# Totem_Teensy.net
KiCad netlist of a schematic drawn in EAGLE
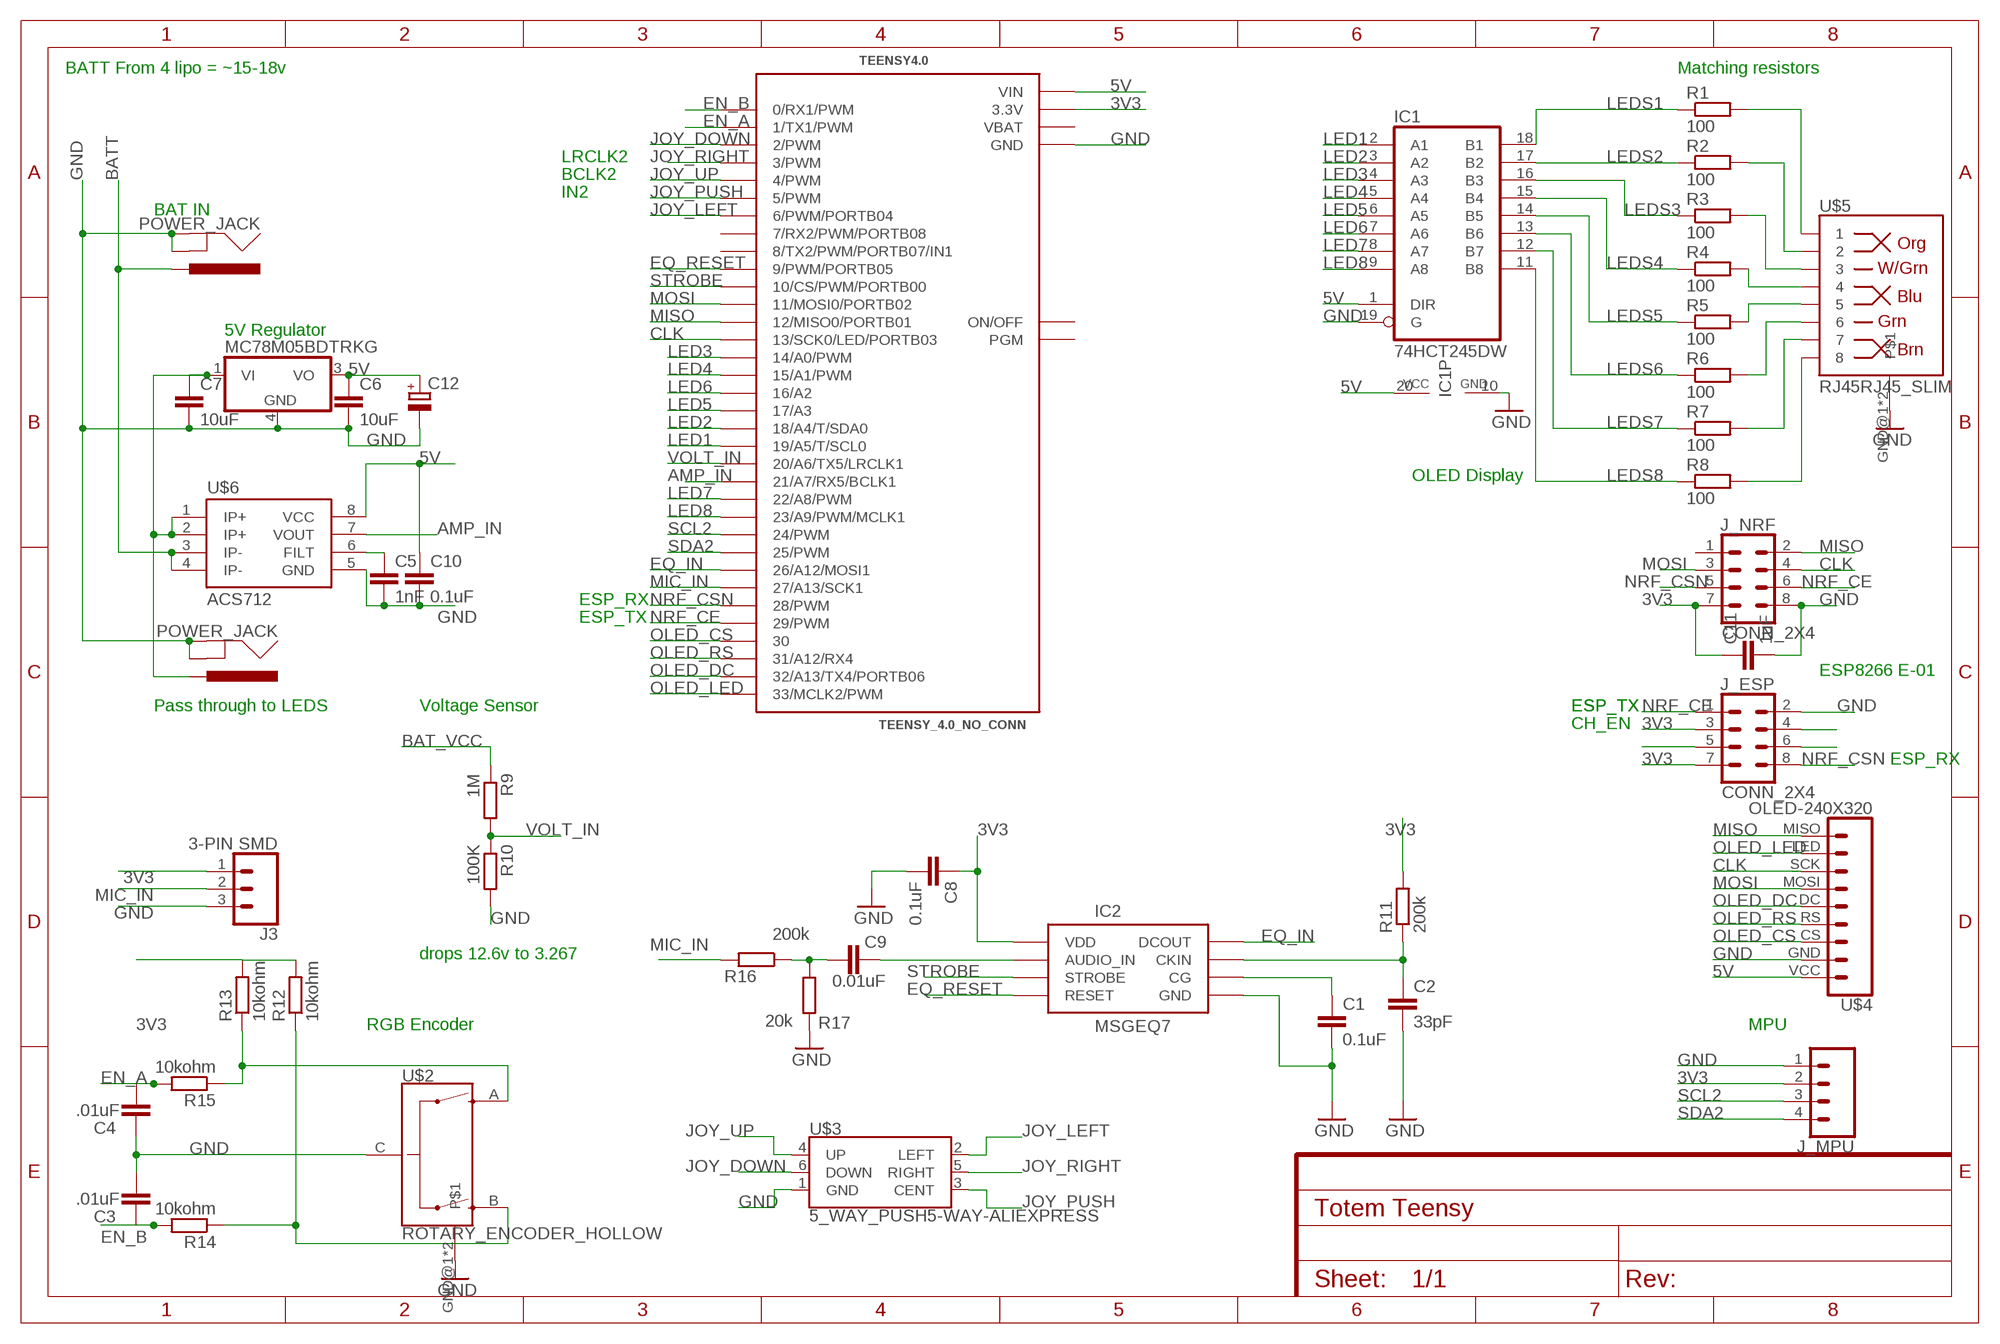
[diagram p0: schematic, sheet 1]

(export (version "E")
  (design (tool "Eeschema 10.0.6"))
  (components
    (comp (ref "C1")
      (value "0.1uF")
      (footprint "eagle-import:C1206")
      (libsource (lib "eagle-import") (part "CC1206"))
    )
    (comp (ref "C2")
      (value "33pF")
      (footprint "eagle-import:C1206")
      (libsource (lib "eagle-import") (part "CC1206"))
    )
    (comp (ref "C3")
      (value ".01uF")
      (footprint "eagle-import:C1206")
      (libsource (lib "eagle-import") (part "CC1206"))
    )
    (comp (ref "C4")
      (value ".01uF")
      (footprint "eagle-import:C1206")
      (libsource (lib "eagle-import") (part "CC1206"))
    )
    (comp (ref "C5")
      (value "1nF")
      (footprint "eagle-import:C1206")
      (libsource (lib "eagle-import") (part "CC1206"))
    )
    (comp (ref "C6")
      (value "10uF")
      (footprint "eagle-import:C1206")
      (libsource (lib "eagle-import") (part "C-EUC1206"))
    )
    (comp (ref "C7")
      (value "10uF")
      (footprint "eagle-import:C1206")
      (libsource (lib "eagle-import") (part "C-EUC1206"))
    )
    (comp (ref "C8")
      (value "0.1uF")
      (footprint "eagle-import:C1206")
      (libsource (lib "eagle-import") (part "CC1206"))
    )
    (comp (ref "C9")
      (value "0.01uF")
      (footprint "eagle-import:C1206")
      (libsource (lib "eagle-import") (part "CC1206"))
    )
    (comp (ref "C10")
      (value "0.1uF")
      (footprint "eagle-import:C1206")
      (libsource (lib "eagle-import") (part "CC1206"))
    )
    (comp (ref "C11")
      (value "1uF")
      (footprint "eagle-import:C1206")
      (libsource (lib "eagle-import") (part "C-EUC1206"))
    )
    (comp (ref "C12")
      (value "CPOL-EUTT2D5L")
      (footprint "eagle-import:TT2D5L")
      (libsource (lib "eagle-import") (part "CPOL-EUTT2D5L"))
    )
    (comp (ref "IC1")
      (value "74HCT245DW")
      (footprint "eagle-import:SO20W")
      (libsource (lib "eagle-import") (part "74245DWHCT"))
    )
    (comp (ref "IC2")
      (value "MSGEQ7DIP")
      (footprint "eagle-import:DIL08")
      (libsource (lib "eagle-import") (part "MSGEQ7DIP"))
    )
    (comp (ref "IC3")
      (value "MC78M05BDTRKG")
      (footprint "eagle-import:DPACK_3")
      (libsource (lib "eagle-import") (part "MC78M05BDTRKG"))
    )
    (comp (ref "J1")
      (value "POWER_JACK")
      (footprint "eagle-import:POWER_JACK_PTH")
      (libsource (lib "eagle-import") (part "POWER_JACK"))
    )
    (comp (ref "J3")
      (value "3-PIN SMD")
      (footprint "eagle-import:JST-3-SMD")
      (libsource (lib "eagle-import") (part "CONN_03JST-SMD"))
    )
    (comp (ref "J7")
      (value "POWER_JACK")
      (footprint "eagle-import:POWER_JACK_PTH")
      (libsource (lib "eagle-import") (part "POWER_JACK"))
    )
    (comp (ref "J_ESP")
      (value "CONN_2X4")
      (footprint "eagle-import:2X4")
      (libsource (lib "eagle-import") (part "CONN_2X4"))
    )
    (comp (ref "J_MPU")
      (value "CONN_04")
      (footprint "eagle-import:1X04")
      (libsource (lib "eagle-import") (part "CONN_04"))
    )
    (comp (ref "J_NRF")
      (value "CONN_2X4")
      (footprint "eagle-import:2X4")
      (libsource (lib "eagle-import") (part "CONN_2X4"))
    )
    (comp (ref "R1")
      (value "100")
      (footprint "eagle-import:R1206")
      (libsource (lib "eagle-import") (part "RR1206"))
    )
    (comp (ref "R2")
      (value "100")
      (footprint "eagle-import:R1206")
      (libsource (lib "eagle-import") (part "RR1206"))
    )
    (comp (ref "R3")
      (value "100")
      (footprint "eagle-import:R1206")
      (libsource (lib "eagle-import") (part "RR1206"))
    )
    (comp (ref "R4")
      (value "100")
      (footprint "eagle-import:R1206")
      (libsource (lib "eagle-import") (part "RR1206"))
    )
    (comp (ref "R5")
      (value "100")
      (footprint "eagle-import:R1206")
      (libsource (lib "eagle-import") (part "RR1206"))
    )
    (comp (ref "R6")
      (value "100")
      (footprint "eagle-import:R1206")
      (libsource (lib "eagle-import") (part "RR1206"))
    )
    (comp (ref "R7")
      (value "100")
      (footprint "eagle-import:R1206")
      (libsource (lib "eagle-import") (part "RR1206"))
    )
    (comp (ref "R8")
      (value "100")
      (footprint "eagle-import:R1206")
      (libsource (lib "eagle-import") (part "RR1206"))
    )
    (comp (ref "R9")
      (value "1M")
      (footprint "eagle-import:M1206")
      (libsource (lib "eagle-import") (part "R-EU_M1206"))
    )
    (comp (ref "R10")
      (value "100K")
      (footprint "eagle-import:M1206")
      (libsource (lib "eagle-import") (part "R-EU_M1206"))
    )
    (comp (ref "R11")
      (value "200k")
      (footprint "eagle-import:R1206")
      (libsource (lib "eagle-import") (part "RR1206"))
    )
    (comp (ref "R12")
      (value "10kohm")
      (footprint "eagle-import:R1206")
      (libsource (lib "eagle-import") (part "RR1206"))
    )
    (comp (ref "R13")
      (value "10kohm")
      (footprint "eagle-import:R1206")
      (libsource (lib "eagle-import") (part "RR1206"))
    )
    (comp (ref "R14")
      (value "10kohm")
      (footprint "eagle-import:R1206")
      (libsource (lib "eagle-import") (part "RR1206"))
    )
    (comp (ref "R15")
      (value "10kohm")
      (footprint "eagle-import:R1206")
      (libsource (lib "eagle-import") (part "RR1206"))
    )
    (comp (ref "R16")
      (value "200k")
      (footprint "eagle-import:R1206")
      (libsource (lib "eagle-import") (part "RR1206"))
    )
    (comp (ref "R17")
      (value "20k")
      (footprint "eagle-import:R1206")
      (libsource (lib "eagle-import") (part "RR1206"))
    )
    (comp (ref "TEENSY4.0")
      (value "TEENSY_4.0_NO_CONN")
      (footprint "eagle-import:TEENSY_4.0")
      (libsource (lib "eagle-import") (part "TEENSY_4.0_NO_CONN"))
    )
    (comp (ref "U$2")
      (value "ROTARY_ENCODER_HOLLOW")
      (footprint "eagle-import:HOLLOW_ENCODER30R")
      (libsource (lib "eagle-import") (part "ROTARY_ENCODER_HOLLOW"))
    )
    (comp (ref "U$3")
      (value "5_WAY_PUSH5-WAY-ALIEXPRESS")
      (footprint "eagle-import:5-WAY_PTH2")
      (libsource (lib "eagle-import") (part "5_WAY_PUSH5-WAY-ALIEXPRESS"))
    )
    (comp (ref "U$4")
      (value "OLED-240X320")
      (footprint "eagle-import:OLED_240X320")
      (libsource (lib "eagle-import") (part "OLED-240X320"))
    )
    (comp (ref "U$5")
      (value "RJ45RJ45_SLIM")
      (footprint "eagle-import:RJ45_SLIM")
      (libsource (lib "eagle-import") (part "RJ45RJ45_SLIM"))
    )
    (comp (ref "U$6")
      (value "ACS712")
      (footprint "eagle-import:SO08")
      (libsource (lib "eagle-import") (part "ACS712"))
    )
  )
  (nets
    (net (code "1") (name "/3V3") (class "Default")
      (node (ref "C11") (pin "1") (pinfunction "1_1") (pintype "passive"))
      (node (ref "C8") (pin "1") (pinfunction "1_1") (pintype "passive"))
      (node (ref "IC2") (pin "1") (pinfunction "VDD_1") (pintype "input"))
      (node (ref "J3") (pin "1") (pinfunction "1_1") (pintype "passive"))
      (node (ref "J_ESP") (pin "3") (pinfunction "3_3") (pintype "passive"))
      (node (ref "J_ESP") (pin "7") (pinfunction "7_7") (pintype "passive"))
      (node (ref "J_MPU") (pin "2") (pinfunction "2_2") (pintype "passive"))
      (node (ref "J_NRF") (pin "7") (pinfunction "7_7") (pintype "passive"))
      (node (ref "R11") (pin "2") (pinfunction "2_2") (pintype "passive"))
      (node (ref "R12") (pin "2") (pinfunction "2_2") (pintype "passive"))
      (node (ref "R13") (pin "2") (pinfunction "2_2") (pintype "passive"))
      (node (ref "TEENSY4.0") (pin "3.3@0") (pinfunction "3.3V_3.3@0") (pintype "power_in"))
      (node (ref "TEENSY4.0") (pin "3.3@1") (pinfunction "3.3V_3.3@1") (pintype "power_in"))
    )
    (net (code "2") (name "/5V") (class "Default")
      (node (ref "C10") (pin "1") (pinfunction "1_1") (pintype "passive"))
      (node (ref "C12") (pin "+") (pinfunction "+_+") (pintype "passive"))
      (node (ref "C6") (pin "1") (pinfunction "1_1") (pintype "passive"))
      (node (ref "IC1") (pin "1") (pinfunction "DIR_1") (pintype "input"))
      (node (ref "IC1") (pin "20") (pinfunction "VCC_20") (pintype "power_in"))
      (node (ref "IC3") (pin "3") (pinfunction "VO_3") (pintype "passive"))
      (node (ref "TEENSY4.0") (pin "VIN") (pinfunction "VIN_VIN") (pintype "power_in"))
      (node (ref "U$4") (pin "VCC") (pinfunction "VCC_VCC") (pintype "passive"))
      (node (ref "U$6") (pin "8") (pinfunction "VCC_8") (pintype "bidirectional"))
    )
    (net (code "3") (name "/AMP_IN") (class "Default")
      (node (ref "TEENSY4.0") (pin "21/A7") (pinfunction "21/A7/RX5/BCLK1_21/A7") (pintype "bidirectional"))
      (node (ref "U$6") (pin "7") (pinfunction "VOUT_7") (pintype "bidirectional"))
    )
    (net (code "4") (name "/BATT") (class "Default")
      (node (ref "J1") (pin "PWR") (pinfunction "PWR_PWR") (pintype "bidirectional"))
      (node (ref "U$6") (pin "3") (pinfunction "IP-_3") (pintype "bidirectional"))
      (node (ref "U$6") (pin "4") (pinfunction "IP-_4") (pintype "bidirectional"))
    )
    (net (code "5") (name "/BAT_VCC") (class "Default")
      (node (ref "C7") (pin "1") (pinfunction "1_1") (pintype "passive"))
      (node (ref "IC3") (pin "1") (pinfunction "VI_1") (pintype "input"))
      (node (ref "J7") (pin "PWR") (pinfunction "PWR_PWR") (pintype "bidirectional"))
      (node (ref "R9") (pin "1") (pinfunction "1_1") (pintype "passive"))
      (node (ref "U$6") (pin "1") (pinfunction "IP+_1") (pintype "bidirectional"))
      (node (ref "U$6") (pin "2") (pinfunction "IP+_2") (pintype "bidirectional"))
    )
    (net (code "6") (name "/CLK") (class "Default")
      (node (ref "J_NRF") (pin "4") (pinfunction "4_4") (pintype "passive"))
      (node (ref "TEENSY4.0") (pin "13") (pinfunction "13/SCK0/LED/PORTB03_13") (pintype "bidirectional"))
      (node (ref "U$4") (pin "SCK") (pinfunction "CLK_SCK") (pintype "passive"))
    )
    (net (code "7") (name "/EN_A") (class "Default")
      (node (ref "C4") (pin "1") (pinfunction "1_1") (pintype "passive"))
      (node (ref "R15") (pin "2") (pinfunction "2_2") (pintype "passive"))
      (node (ref "TEENSY4.0") (pin "1") (pinfunction "1/TX1/PWM_1") (pintype "bidirectional"))
    )
    (net (code "8") (name "/EN_B") (class "Default")
      (node (ref "C3") (pin "2") (pinfunction "2_2") (pintype "passive"))
      (node (ref "R14") (pin "2") (pinfunction "2_2") (pintype "passive"))
      (node (ref "TEENSY4.0") (pin "0") (pinfunction "0/RX1/PWM_0") (pintype "bidirectional"))
    )
    (net (code "9") (name "/EQ_IN") (class "Default")
      (node (ref "IC2") (pin "3") (pinfunction "DCOUT_3") (pintype "bidirectional"))
      (node (ref "TEENSY4.0") (pin "26") (pinfunction "26/A12/MOSI1_26") (pintype "bidirectional"))
    )
    (net (code "10") (name "/EQ_RESET") (class "Default")
      (node (ref "IC2") (pin "7") (pinfunction "RESET_7") (pintype "input"))
      (node (ref "TEENSY4.0") (pin "9") (pinfunction "9/PWM/PORTB05_9") (pintype "bidirectional"))
    )
    (net (code "11") (name "/JOY_DOWN") (class "Default")
      (node (ref "TEENSY4.0") (pin "2") (pinfunction "2/PWM_2") (pintype "bidirectional"))
      (node (ref "U$3") (pin "6") (pinfunction "DOWN_6") (pintype "bidirectional"))
    )
    (net (code "12") (name "/JOY_LEFT") (class "Default")
      (node (ref "TEENSY4.0") (pin "6") (pinfunction "6/PWM/PORTB04_6") (pintype "bidirectional"))
      (node (ref "U$3") (pin "2") (pinfunction "LEFT_2") (pintype "bidirectional"))
    )
    (net (code "13") (name "/JOY_PUSH") (class "Default")
      (node (ref "TEENSY4.0") (pin "5") (pinfunction "5/PWM_5") (pintype "bidirectional"))
      (node (ref "U$3") (pin "3") (pinfunction "CENT_3") (pintype "bidirectional"))
    )
    (net (code "14") (name "/JOY_RIGHT") (class "Default")
      (node (ref "TEENSY4.0") (pin "3") (pinfunction "3/PWM_3") (pintype "bidirectional"))
      (node (ref "U$3") (pin "5") (pinfunction "RIGHT_5") (pintype "bidirectional"))
    )
    (net (code "15") (name "/JOY_UP") (class "Default")
      (node (ref "TEENSY4.0") (pin "4") (pinfunction "4/PWM_4") (pintype "bidirectional"))
      (node (ref "U$3") (pin "4") (pinfunction "UP_4") (pintype "bidirectional"))
    )
    (net (code "16") (name "/LED1") (class "Default")
      (node (ref "IC1") (pin "2") (pinfunction "A1_2") (pintype "bidirectional"))
      (node (ref "TEENSY4.0") (pin "19/A5") (pinfunction "19/A5/T/SCL0_19/A5") (pintype "bidirectional"))
    )
    (net (code "17") (name "/LED2") (class "Default")
      (node (ref "IC1") (pin "3") (pinfunction "A2_3") (pintype "bidirectional"))
      (node (ref "TEENSY4.0") (pin "18/A4") (pinfunction "18/A4/T/SDA0_18/A4") (pintype "bidirectional"))
    )
    (net (code "18") (name "/LED3") (class "Default")
      (node (ref "IC1") (pin "4") (pinfunction "A3_4") (pintype "bidirectional"))
      (node (ref "TEENSY4.0") (pin "14/A0") (pinfunction "14/A0/PWM_14/A0") (pintype "bidirectional"))
    )
    (net (code "19") (name "/LED4") (class "Default")
      (node (ref "IC1") (pin "5") (pinfunction "A4_5") (pintype "bidirectional"))
      (node (ref "TEENSY4.0") (pin "15/A1") (pinfunction "15/A1/PWM_15/A1") (pintype "bidirectional"))
    )
    (net (code "20") (name "/LED5") (class "Default")
      (node (ref "IC1") (pin "6") (pinfunction "A5_6") (pintype "bidirectional"))
      (node (ref "TEENSY4.0") (pin "17/A3") (pinfunction "17/A3_17/A3") (pintype "bidirectional"))
    )
    (net (code "21") (name "/LED6") (class "Default")
      (node (ref "IC1") (pin "7") (pinfunction "A6_7") (pintype "bidirectional"))
      (node (ref "TEENSY4.0") (pin "16/A2") (pinfunction "16/A2_16/A2") (pintype "bidirectional"))
    )
    (net (code "22") (name "/LED7") (class "Default")
      (node (ref "IC1") (pin "8") (pinfunction "A7_8") (pintype "bidirectional"))
      (node (ref "TEENSY4.0") (pin "22/A8") (pinfunction "22/A8/PWM_22/A8") (pintype "bidirectional"))
    )
    (net (code "23") (name "/LED8") (class "Default")
      (node (ref "IC1") (pin "9") (pinfunction "A8_9") (pintype "bidirectional"))
      (node (ref "TEENSY4.0") (pin "23/A9") (pinfunction "23/A9/PWM/MCLK1_23/A9") (pintype "bidirectional"))
    )
    (net (code "24") (name "/LEDS1") (class "Default")
      (node (ref "IC1") (pin "18") (pinfunction "B1_18") (pintype "bidirectional"))
      (node (ref "R1") (pin "1") (pinfunction "1_1") (pintype "passive"))
    )
    (net (code "25") (name "/LEDS2") (class "Default")
      (node (ref "IC1") (pin "17") (pinfunction "B2_17") (pintype "bidirectional"))
      (node (ref "R2") (pin "1") (pinfunction "1_1") (pintype "passive"))
    )
    (net (code "26") (name "/LEDS3") (class "Default")
      (node (ref "IC1") (pin "16") (pinfunction "B3_16") (pintype "bidirectional"))
      (node (ref "R3") (pin "1") (pinfunction "1_1") (pintype "passive"))
    )
    (net (code "27") (name "/LEDS4") (class "Default")
      (node (ref "IC1") (pin "15") (pinfunction "B4_15") (pintype "bidirectional"))
      (node (ref "R4") (pin "1") (pinfunction "1_1") (pintype "passive"))
    )
    (net (code "28") (name "/LEDS5") (class "Default")
      (node (ref "IC1") (pin "14") (pinfunction "B5_14") (pintype "bidirectional"))
      (node (ref "R5") (pin "1") (pinfunction "1_1") (pintype "passive"))
    )
    (net (code "29") (name "/LEDS6") (class "Default")
      (node (ref "IC1") (pin "13") (pinfunction "B6_13") (pintype "bidirectional"))
      (node (ref "R6") (pin "1") (pinfunction "1_1") (pintype "passive"))
    )
    (net (code "30") (name "/LEDS7") (class "Default")
      (node (ref "IC1") (pin "12") (pinfunction "B7_12") (pintype "bidirectional"))
      (node (ref "R7") (pin "1") (pinfunction "1_1") (pintype "passive"))
    )
    (net (code "31") (name "/LEDS8") (class "Default")
      (node (ref "IC1") (pin "11") (pinfunction "B8_11") (pintype "bidirectional"))
      (node (ref "R8") (pin "1") (pinfunction "1_1") (pintype "passive"))
    )
    (net (code "32") (name "/MIC_IN") (class "Default")
      (node (ref "J3") (pin "2") (pinfunction "2_2") (pintype "passive"))
      (node (ref "R16") (pin "2") (pinfunction "2_2") (pintype "passive"))
      (node (ref "TEENSY4.0") (pin "27") (pinfunction "27/A13/SCK1_27") (pintype "bidirectional"))
    )
    (net (code "33") (name "/MISO") (class "Default")
      (node (ref "J_NRF") (pin "2") (pinfunction "2_2") (pintype "passive"))
      (node (ref "TEENSY4.0") (pin "12") (pinfunction "12/MISO0/PORTB01_12") (pintype "bidirectional"))
      (node (ref "U$4") (pin "MISO") (pinfunction "MISO_MISO") (pintype "passive"))
    )
    (net (code "34") (name "/MOSI") (class "Default")
      (node (ref "J_NRF") (pin "3") (pinfunction "3_3") (pintype "passive"))
      (node (ref "TEENSY4.0") (pin "11") (pinfunction "11/MOSI0/PORTB02_11") (pintype "bidirectional"))
      (node (ref "U$4") (pin "MOSI") (pinfunction "MOSI_MOSI") (pintype "passive"))
    )
    (net (code "35") (name "/NRF_CE") (class "Default")
      (node (ref "J_ESP") (pin "1") (pinfunction "1_1") (pintype "passive"))
      (node (ref "J_NRF") (pin "6") (pinfunction "6_6") (pintype "passive"))
      (node (ref "TEENSY4.0") (pin "29") (pinfunction "29/PWM_29") (pintype "bidirectional"))
    )
    (net (code "36") (name "/NRF_CSN") (class "Default")
      (node (ref "J_ESP") (pin "8") (pinfunction "8_8") (pintype "passive"))
      (node (ref "J_NRF") (pin "5") (pinfunction "5_5") (pintype "passive"))
      (node (ref "TEENSY4.0") (pin "28") (pinfunction "28/PWM_28") (pintype "bidirectional"))
    )
    (net (code "37") (name "/OLED_CS") (class "Default")
      (node (ref "TEENSY4.0") (pin "30") (pinfunction "30_30") (pintype "bidirectional"))
      (node (ref "U$4") (pin "CS") (pinfunction "CS_CS") (pintype "passive"))
    )
    (net (code "38") (name "/OLED_DC") (class "Default")
      (node (ref "TEENSY4.0") (pin "32") (pinfunction "32/A13/TX4/PORTB06_32") (pintype "bidirectional"))
      (node (ref "U$4") (pin "DC") (pinfunction "DC_DC") (pintype "passive"))
    )
    (net (code "39") (name "/OLED_LED") (class "Default")
      (node (ref "TEENSY4.0") (pin "33") (pinfunction "33/MCLK2/PWM_33") (pintype "bidirectional"))
      (node (ref "U$4") (pin "LED") (pinfunction "LED_LED") (pintype "passive"))
    )
    (net (code "40") (name "/OLED_RS") (class "Default")
      (node (ref "TEENSY4.0") (pin "31") (pinfunction "31/A12/RX4_31") (pintype "bidirectional"))
      (node (ref "U$4") (pin "RS") (pinfunction "RS_RS") (pintype "passive"))
    )
    (net (code "41") (name "/SCL2") (class "Default")
      (node (ref "J_MPU") (pin "3") (pinfunction "3_3") (pintype "passive"))
      (node (ref "TEENSY4.0") (pin "24") (pinfunction "24/PWM_24") (pintype "bidirectional"))
    )
    (net (code "42") (name "/SDA2") (class "Default")
      (node (ref "J_MPU") (pin "4") (pinfunction "4_4") (pintype "passive"))
      (node (ref "TEENSY4.0") (pin "25") (pinfunction "25/PWM_25") (pintype "bidirectional"))
    )
    (net (code "43") (name "/STROBE") (class "Default")
      (node (ref "IC2") (pin "4") (pinfunction "STROBE_4") (pintype "input"))
      (node (ref "TEENSY4.0") (pin "10") (pinfunction "10/CS/PWM/PORTB00_10") (pintype "bidirectional"))
    )
    (net (code "44") (name "/VBAT") (class "Default")
      (node (ref "TEENSY4.0") (pin "VBAT") (pinfunction "VBAT_VBAT") (pintype "power_in"))
    )
    (net (code "45") (name "/VOLT_IN") (class "Default")
      (node (ref "R10") (pin "1") (pinfunction "1_1") (pintype "passive"))
      (node (ref "R9") (pin "2") (pinfunction "2_2") (pintype "passive"))
      (node (ref "TEENSY4.0") (pin "20/A6") (pinfunction "20/A6/TX5/LRCLK1_20/A6") (pintype "bidirectional"))
    )
    (net (code "46") (name "GND") (class "Default")
      (node (ref "C1") (pin "2") (pinfunction "2_2") (pintype "passive"))
      (node (ref "C10") (pin "2") (pinfunction "2_2") (pintype "passive"))
      (node (ref "C11") (pin "2") (pinfunction "2_2") (pintype "passive"))
      (node (ref "C12") (pin "-") (pinfunction "-_-") (pintype "passive"))
      (node (ref "C2") (pin "2") (pinfunction "2_2") (pintype "passive"))
      (node (ref "C3") (pin "1") (pinfunction "1_1") (pintype "passive"))
      (node (ref "C4") (pin "2") (pinfunction "2_2") (pintype "passive"))
      (node (ref "C5") (pin "2") (pinfunction "2_2") (pintype "passive"))
      (node (ref "C6") (pin "2") (pinfunction "2_2") (pintype "passive"))
      (node (ref "C7") (pin "2") (pinfunction "2_2") (pintype "passive"))
      (node (ref "C8") (pin "2") (pinfunction "2_2") (pintype "passive"))
      (node (ref "IC1") (pin "10") (pinfunction "GND_10") (pintype "power_in"))
      (node (ref "IC1") (pin "19") (pinfunction "G_19") (pintype "input"))
      (node (ref "IC2") (pin "2") (pinfunction "GND_2") (pintype "bidirectional"))
      (node (ref "IC3") (pin "4") (pinfunction "GND_4") (pintype "passive"))
      (node (ref "J1") (pin "GND") (pinfunction "GND_GND") (pintype "bidirectional"))
      (node (ref "J1") (pin "GNDBREAK") (pinfunction "GNDBREAK_GNDBREAK") (pintype "bidirectional"))
      (node (ref "J3") (pin "3") (pinfunction "3_3") (pintype "passive"))
      (node (ref "J7") (pin "GND") (pinfunction "GND_GND") (pintype "bidirectional"))
      (node (ref "J7") (pin "GNDBREAK") (pinfunction "GNDBREAK_GNDBREAK") (pintype "bidirectional"))
      (node (ref "J_ESP") (pin "2") (pinfunction "2_2") (pintype "passive"))
      (node (ref "J_MPU") (pin "1") (pinfunction "1_1") (pintype "passive"))
      (node (ref "J_NRF") (pin "8") (pinfunction "8_8") (pintype "passive"))
      (node (ref "R10") (pin "2") (pinfunction "2_2") (pintype "passive"))
      (node (ref "R17") (pin "2") (pinfunction "2_2") (pintype "passive"))
      (node (ref "TEENSY4.0") (pin "GND@0") (pinfunction "GND_GND@0") (pintype "power_in"))
      (node (ref "TEENSY4.0") (pin "GND@1") (pinfunction "GND_GND@1") (pintype "power_in"))
      (node (ref "TEENSY4.0") (pin "GND@2") (pinfunction "GND_GND@2") (pintype "power_in"))
      (node (ref "U$2") (pin "C") (pinfunction "C_C") (pintype "bidirectional"))
      (node (ref "U$2") (pin "GND@1") (pinfunction "P$1_GND@1") (pintype "power_in"))
      (node (ref "U$2") (pin "GND@2") (pinfunction "P$1_GND@2") (pintype "power_in"))
      (node (ref "U$3") (pin "1") (pinfunction "GND_1") (pintype "bidirectional"))
      (node (ref "U$4") (pin "GND") (pinfunction "GND_GND") (pintype "passive"))
      (node (ref "U$5") (pin "GND@1") (pinfunction "P$1_GND@1") (pintype "power_in"))
      (node (ref "U$5") (pin "GND@2") (pinfunction "P$1_GND@2") (pintype "power_in"))
      (node (ref "U$6") (pin "5") (pinfunction "GND_5") (pintype "bidirectional"))
    )
    (net (code "47") (name "Net-(C9-Pad2)") (class "Default")
      (node (ref "C9") (pin "2") (pinfunction "2_2") (pintype "passive"))
      (node (ref "R16") (pin "1") (pinfunction "1_1") (pintype "passive"))
      (node (ref "R17") (pin "1") (pinfunction "1_1") (pintype "passive"))
    )
    (net (code "48") (name "Net-(IC2-AUDIO_IN)") (class "Default")
      (node (ref "C9") (pin "1") (pinfunction "1_1") (pintype "passive"))
      (node (ref "IC2") (pin "5") (pinfunction "AUDIO_IN_5") (pintype "input"))
    )
    (net (code "49") (name "Net-(IC2-CG)") (class "Default")
      (node (ref "C1") (pin "1") (pinfunction "1_1") (pintype "passive"))
      (node (ref "IC2") (pin "6") (pinfunction "CG_6") (pintype "bidirectional"))
    )
    (net (code "50") (name "Net-(IC2-CKIN)") (class "Default")
      (node (ref "C2") (pin "1") (pinfunction "1_1") (pintype "passive"))
      (node (ref "IC2") (pin "8") (pinfunction "CKIN_8") (pintype "bidirectional"))
      (node (ref "R11") (pin "1") (pinfunction "1_1") (pintype "passive"))
    )
    (net (code "51") (name "Net-(R12-Pad1)") (class "Default")
      (node (ref "R12") (pin "1") (pinfunction "1_1") (pintype "passive"))
      (node (ref "R14") (pin "1") (pinfunction "1_1") (pintype "passive"))
      (node (ref "U$2") (pin "B") (pinfunction "B_B") (pintype "bidirectional"))
    )
    (net (code "52") (name "Net-(R13-Pad1)") (class "Default")
      (node (ref "R13") (pin "1") (pinfunction "1_1") (pintype "passive"))
      (node (ref "R15") (pin "1") (pinfunction "1_1") (pintype "passive"))
      (node (ref "U$2") (pin "A") (pinfunction "A_A") (pintype "bidirectional"))
    )
    (net (code "53") (name "Net-(U$5-1)") (class "Default")
      (node (ref "R1") (pin "2") (pinfunction "2_2") (pintype "passive"))
      (node (ref "U$5") (pin "8") (pinfunction "1_8") (pintype "bidirectional"))
    )
    (net (code "54") (name "Net-(U$5-2)") (class "Default")
      (node (ref "R2") (pin "2") (pinfunction "2_2") (pintype "passive"))
      (node (ref "U$5") (pin "7") (pinfunction "2_7") (pintype "bidirectional"))
    )
    (net (code "55") (name "Net-(U$5-3)") (class "Default")
      (node (ref "R3") (pin "2") (pinfunction "2_2") (pintype "passive"))
      (node (ref "U$5") (pin "6") (pinfunction "3_6") (pintype "bidirectional"))
    )
    (net (code "56") (name "Net-(U$5-4)") (class "Default")
      (node (ref "R4") (pin "2") (pinfunction "2_2") (pintype "passive"))
      (node (ref "U$5") (pin "5") (pinfunction "4_5") (pintype "bidirectional"))
    )
    (net (code "57") (name "Net-(U$5-5)") (class "Default")
      (node (ref "R5") (pin "2") (pinfunction "2_2") (pintype "passive"))
      (node (ref "U$5") (pin "4") (pinfunction "5_4") (pintype "bidirectional"))
    )
    (net (code "58") (name "Net-(U$5-6)") (class "Default")
      (node (ref "R6") (pin "2") (pinfunction "2_2") (pintype "passive"))
      (node (ref "U$5") (pin "3") (pinfunction "6_3") (pintype "bidirectional"))
    )
    (net (code "59") (name "Net-(U$5-7)") (class "Default")
      (node (ref "R7") (pin "2") (pinfunction "2_2") (pintype "passive"))
      (node (ref "U$5") (pin "2") (pinfunction "7_2") (pintype "bidirectional"))
    )
    (net (code "60") (name "Net-(U$5-8)") (class "Default")
      (node (ref "R8") (pin "2") (pinfunction "2_2") (pintype "passive"))
      (node (ref "U$5") (pin "1") (pinfunction "8_1") (pintype "bidirectional"))
    )
    (net (code "61") (name "Net-(U$6-FILT)") (class "Default")
      (node (ref "C5") (pin "1") (pinfunction "1_1") (pintype "passive"))
      (node (ref "U$6") (pin "6") (pinfunction "FILT_6") (pintype "bidirectional"))
    )
    (net (code "62") (name "unconnected-(J_ESP-Pad4)") (class "Default")
      (node (ref "J_ESP") (pin "4") (pinfunction "4_4") (pintype "passive"))
    )
    (net (code "63") (name "unconnected-(J_ESP-Pad5)") (class "Default")
      (node (ref "J_ESP") (pin "5") (pinfunction "5_5") (pintype "passive"))
    )
    (net (code "64") (name "unconnected-(J_ESP-Pad6)") (class "Default")
      (node (ref "J_ESP") (pin "6") (pinfunction "6_6") (pintype "passive"))
    )
    (net (code "65") (name "unconnected-(J_NRF-Pad1)") (class "Default")
      (node (ref "J_NRF") (pin "1") (pinfunction "1_1") (pintype "passive"))
    )
    (net (code "66") (name "unconnected-(TEENSY4.0-7{slash}RX2{slash}PWM{slash}PORTB08-Pad7)") (class "Default")
      (node (ref "TEENSY4.0") (pin "7") (pinfunction "7/RX2/PWM/PORTB08_7") (pintype "bidirectional"))
    )
    (net (code "67") (name "unconnected-(TEENSY4.0-8{slash}TX2{slash}PWM{slash}PORTB07{slash}IN1-Pad8)") (class "Default")
      (node (ref "TEENSY4.0") (pin "8") (pinfunction "8/TX2/PWM/PORTB07/IN1_8") (pintype "bidirectional"))
    )
    (net (code "68") (name "unconnected-(TEENSY4.0-PadON{slash}OFF)") (class "Default")
      (node (ref "TEENSY4.0") (pin "ON/OFF") (pinfunction "ON/OFF_ON/OFF") (pintype "bidirectional"))
    )
    (net (code "69") (name "unconnected-(TEENSY4.0-PadPGM)") (class "Default")
      (node (ref "TEENSY4.0") (pin "PGM") (pinfunction "PGM_PGM") (pintype "bidirectional"))
    )
  )
)
